# LM2596_MainBoard_V0_1.net
KiCad netlist of a schematic drawn in EAGLE
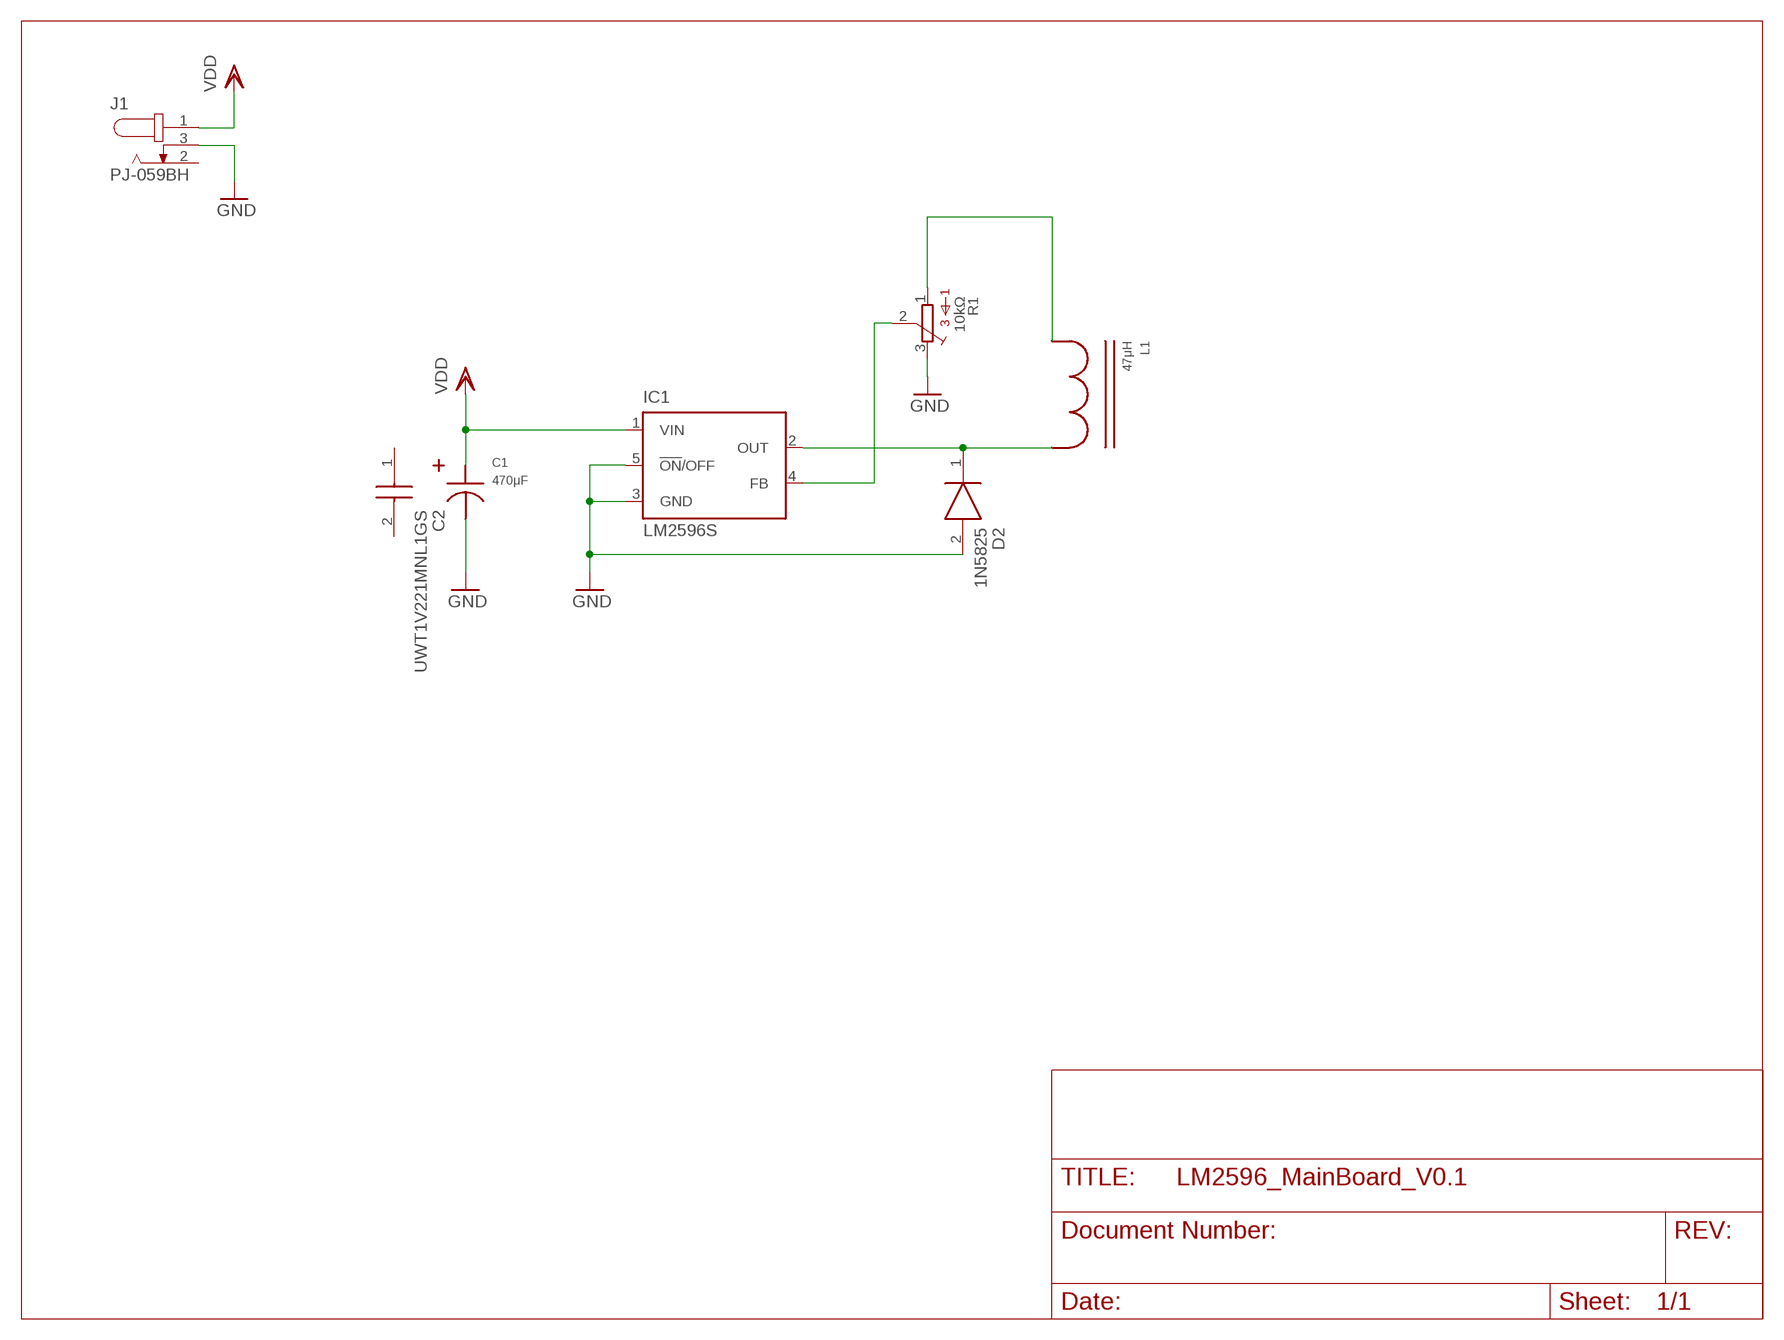
[diagram p0: schematic, sheet 1]

(export (version "E")
  (design (tool "Eeschema 10.0.6"))
  (components
    (comp (ref "C1")
      (value "470μF")
      (footprint "eagle-import:LELON_SMD_CAP_12P5")
      (libsource (lib "eagle-import") (part "VE-471M1HTR-1316"))
    )
    (comp (ref "C2")
      (value "UWT1V221MNL1GS")
      (footprint "eagle-import:UWT(8X10)")
      (fields (field (name "MOUSER_PART_NUMBER") "647-UWT1V221MNL1S"))
      (libsource (lib "eagle-import") (part "UWT1V221MNL1GS"))
    )
    (comp (ref "D2")
      (value "1N5825")
      (footprint "eagle-import:DIOAD4191W142L1143D762")
      (fields (field (name "MOUSER_PART_NUMBER") "494-1N5825"))
      (libsource (lib "eagle-import") (part "1N5825"))
    )
    (comp (ref "IC1")
      (value "LM2596S")
      (footprint "eagle-import:TO263-5")
      (fields (field (name "MF") "NATIONAL SEMICONDUCTOR") (field (name "MPN") "LM2596S-ADJ/NOPB"))
      (libsource (lib "eagle-import") (part "LM2596S"))
    )
    (comp (ref "J1")
      (value "PJ-059BH")
      (footprint "eagle-import:CUI_PJ-059BH")
      (fields (field (name "MANUFACTURER") "CUI INC"))
      (libsource (lib "eagle-import") (part "PJ-059BH"))
    )
    (comp (ref "L1")
      (value "47μH")
      (footprint "eagle-import:HA78-60")
      (libsource (lib "eagle-import") (part "HA78-60470LFTR13"))
    )
    (comp (ref "R1")
      (value "10kΩ")
      (footprint "eagle-import:3386W")
      (libsource (lib "eagle-import") (part "3386-W"))
    )
  )
  (nets
    (net (code "1") (name "GND") (class "Default")
      (node (ref "C1") (pin "N") (pinfunction "N_N") (pintype "bidirectional"))
      (node (ref "D2") (pin "2") (pinfunction "A_2") (pintype "bidirectional"))
      (node (ref "IC1") (pin "3") (pinfunction "GND_3") (pintype "power_in"))
      (node (ref "IC1") (pin "5") (pinfunction "~{ON}/OFF_5") (pintype "input"))
      (node (ref "J1") (pin "3") (pinfunction "3_3") (pintype "passive"))
      (node (ref "R1") (pin "3") (pinfunction "3_3") (pintype "passive"))
    )
    (net (code "2") (name "Net-(D2-K)") (class "Default")
      (node (ref "D2") (pin "1") (pinfunction "K_1") (pintype "bidirectional"))
      (node (ref "IC1") (pin "2") (pinfunction "OUT_2") (pintype "output"))
      (node (ref "L1") (pin "P$2") (pinfunction "P$2_P$2") (pintype "bidirectional"))
    )
    (net (code "3") (name "Net-(IC1-FB)") (class "Default")
      (node (ref "IC1") (pin "4") (pinfunction "FB_4") (pintype "input"))
      (node (ref "R1") (pin "2") (pinfunction "2_2") (pintype "passive"))
    )
    (net (code "4") (name "Net-(L1-PadP$1)") (class "Default")
      (node (ref "L1") (pin "P$1") (pinfunction "P$1_P$1") (pintype "bidirectional"))
      (node (ref "R1") (pin "1") (pinfunction "1_1") (pintype "passive"))
    )
    (net (code "5") (name "VDD") (class "Default")
      (node (ref "C1") (pin "P") (pinfunction "P_P") (pintype "bidirectional"))
      (node (ref "IC1") (pin "1") (pinfunction "VIN_1") (pintype "input"))
      (node (ref "J1") (pin "1") (pinfunction "1_1") (pintype "passive"))
    )
    (net (code "6") (name "unconnected-(C2-+-Pad2)") (class "Default")
      (node (ref "C2") (pin "2") (pinfunction "+_2") (pintype "bidirectional"))
    )
    (net (code "7") (name "unconnected-(C2---Pad1)") (class "Default")
      (node (ref "C2") (pin "1") (pinfunction "-_1") (pintype "bidirectional"))
    )
    (net (code "8") (name "unconnected-(J1-Pad2)") (class "Default")
      (node (ref "J1") (pin "2") (pinfunction "2_2") (pintype "passive"))
    )
  )
)
